# Tag201_GangProgrammerRev2.net
KiCad netlist of a schematic drawn in Altium Designer
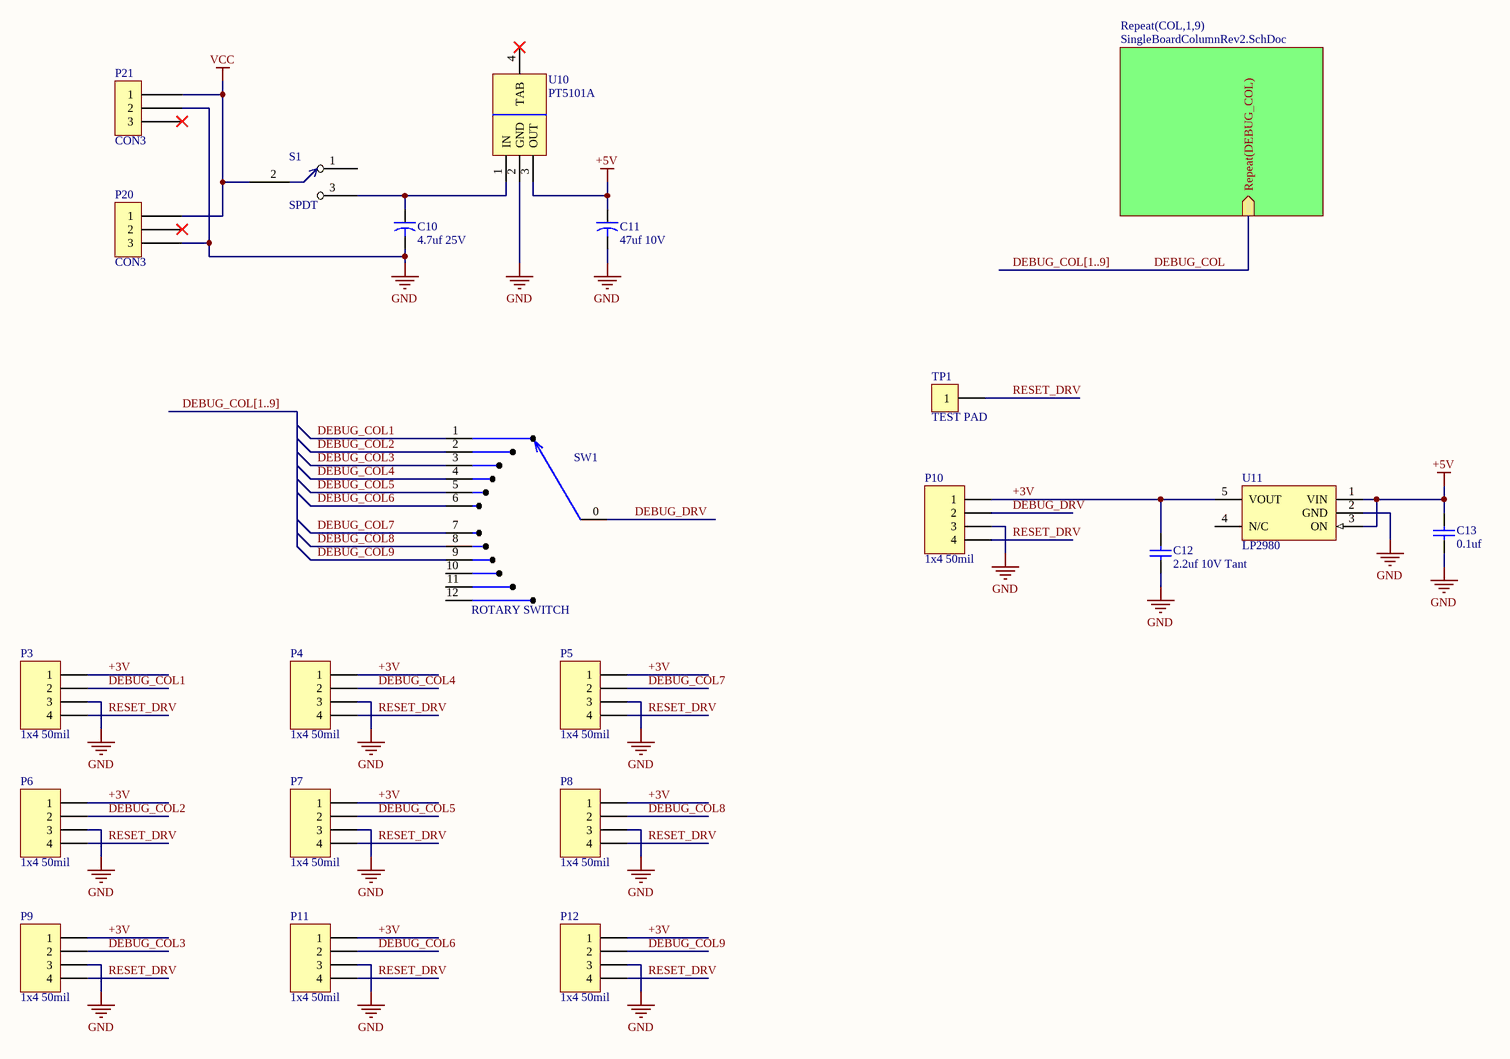
[diagram p0: Tag201_GangProgrammerRev2.SchDoc]

(export (version "E")
  (design (tool "Eeschema 10.0.6"))
  (components
    (comp (ref "C10")
      (value "4.7uf 25V")
      (footprint "CAP C CASE_041412")
      (description "Capacitor")
      (fields (field (name "PARTNO") "T491A475M025AT"))
      (libsource (lib "Miscellaneous Devices") (part "Cap2"))
    )
    (comp (ref "C11")
      (value "47uf 10V")
      (footprint "CAP D CASE_030205")
      (description "Capacitor")
      (fields (field (name "PARTNO") "TAJC476K010RNJ"))
      (libsource (lib "Miscellaneous Devices") (part "Cap2"))
    )
    (comp (ref "C12")
      (value "2.2uf 10V Tant")
      (footprint "CAP A CASE_030205")
      (description "Capacitor")
      (fields (field (name "PARTNO") "F931A225MAA"))
      (libsource (lib "Miscellaneous Devices") (part "Cap"))
    )
    (comp (ref "C13")
      (value "0.1uf")
      (footprint "0603_072205")
      (description "Capacitor")
      (fields (field (name "PARTNO") "C0603C104Z3VACTU"))
      (libsource (lib "Miscellaneous Devices") (part "Cap"))
    )
    (comp (ref "P3")
      (value "1x4 50mil")
      (footprint "1X4 HEADER_50mil_071411")
      (description "Header, 4-Pin")
      (libsource (lib "Miscellaneous Connectors") (part "Header 4"))
    )
    (comp (ref "P4")
      (value "1x4 50mil")
      (footprint "1X4 HEADER_50mil_071411")
      (description "Header, 4-Pin")
      (libsource (lib "Miscellaneous Connectors") (part "Header 4"))
    )
    (comp (ref "P5")
      (value "1x4 50mil")
      (footprint "1X4 HEADER_50mil_071411")
      (description "Header, 4-Pin")
      (libsource (lib "Miscellaneous Connectors") (part "Header 4"))
    )
    (comp (ref "P6")
      (value "1x4 50mil")
      (footprint "1X4 HEADER_50mil_071411")
      (description "Header, 4-Pin")
      (libsource (lib "Miscellaneous Connectors") (part "Header 4"))
    )
    (comp (ref "P7")
      (value "1x4 50mil")
      (footprint "1X4 HEADER_50mil_071411")
      (description "Header, 4-Pin")
      (libsource (lib "Miscellaneous Connectors") (part "Header 4"))
    )
    (comp (ref "P8")
      (value "1x4 50mil")
      (footprint "1X4 HEADER_50mil_071411")
      (description "Header, 4-Pin")
      (libsource (lib "Miscellaneous Connectors") (part "Header 4"))
    )
    (comp (ref "P9")
      (value "1x4 50mil")
      (footprint "1X4 HEADER_50mil_071411")
      (description "Header, 4-Pin")
      (libsource (lib "Miscellaneous Connectors") (part "Header 4"))
    )
    (comp (ref "P10")
      (value "1x4 50mil")
      (footprint "1X4 HEADER_50mil_071411")
      (description "Header, 4-Pin")
      (libsource (lib "Miscellaneous Connectors") (part "Header 4"))
    )
    (comp (ref "P11")
      (value "1x4 50mil")
      (footprint "1X4 HEADER_50mil_071411")
      (description "Header, 4-Pin")
      (libsource (lib "Miscellaneous Connectors") (part "Header 4"))
    )
    (comp (ref "P12")
      (value "1x4 50mil")
      (footprint "1X4 HEADER_50mil_071411")
      (description "Header, 4-Pin")
      (libsource (lib "Miscellaneous Connectors") (part "Header 4"))
    )
    (comp (ref "P20")
      (value "CON3")
      (footprint "POWER JACK_SMALLHOLE_022110")
      (fields (field (name "PARTNO") "PJ-102A"))
      (libsource (lib "Common") (part "CON3"))
    )
    (comp (ref "P21")
      (value "CON3")
      (footprint "Power Jack_SMT_071312")
      (fields (field (name "PARTNO") "PJ-002A-SMT"))
      (libsource (lib "Common") (part "CON3"))
    )
    (comp (ref "S1")
      (value "SPDT")
      (footprint "CnK_TseriesSPDT_Toggle_040512")
      (fields (field (name "PARTNO") "T102SHCQE"))
      (libsource (lib "Common") (part "SWITCH SPST"))
    )
    (comp (ref "SW1")
      (value "ROTARY SWITCH")
      (footprint "SWITCH_ROTARY_1P12T_101912")
      (fields (field (name "MFG") "Grayhill"))
      (libsource (lib "Common") (part "SwitchRotary1P12T"))
    )
    (comp (ref "TP1")
      (value "TEST PAD")
      (footprint "TestPoint52x32")
      (description "Connector")
      (libsource (lib "Common") (part "CON1"))
    )
    (comp (ref "U10")
      (value "PT5101A")
      (footprint "TI_PowerTrendsPT_061812")
      (libsource (lib "Common") (part "LM340T"))
    )
    (comp (ref "U11")
      (value "LP2980")
      (footprint "SOT25_030205")
      (fields (field (name "PARTNO") "LP2980AIM5-3.3/NOPB"))
      (libsource (lib "Common") (part "LP2985"))
    )
  )
  (nets
    (net (code "1") (name "+5V") (class "Default")
      (node (ref "C11") (pin "1") (pinfunction "1_1") (pintype "passive"))
      (node (ref "C13") (pin "1") (pinfunction "1_1") (pintype "passive"))
      (node (ref "U10") (pin "3") (pinfunction "OUT_3") (pintype "passive"))
      (node (ref "U11") (pin "1") (pinfunction "VIN_1") (pintype "power_in"))
      (node (ref "U11") (pin "3") (pinfunction "ON_3") (pintype "input"))
    )
    (net (code "2") (name "/+3V") (class "Default")
      (node (ref "C12") (pin "1") (pinfunction "1_1") (pintype "passive"))
      (node (ref "P10") (pin "1") (pinfunction "1_1") (pintype "passive"))
      (node (ref "P11") (pin "1") (pinfunction "1_1") (pintype "passive"))
      (node (ref "P12") (pin "1") (pinfunction "1_1") (pintype "passive"))
      (node (ref "P3") (pin "1") (pinfunction "1_1") (pintype "passive"))
      (node (ref "P4") (pin "1") (pinfunction "1_1") (pintype "passive"))
      (node (ref "P5") (pin "1") (pinfunction "1_1") (pintype "passive"))
      (node (ref "P6") (pin "1") (pinfunction "1_1") (pintype "passive"))
      (node (ref "P7") (pin "1") (pinfunction "1_1") (pintype "passive"))
      (node (ref "P8") (pin "1") (pinfunction "1_1") (pintype "passive"))
      (node (ref "P9") (pin "1") (pinfunction "1_1") (pintype "passive"))
      (node (ref "U11") (pin "5") (pinfunction "VOUT_5") (pintype "power_in"))
    )
    (net (code "4") (name "/DEBUG_COL1") (class "Default")
      (node (ref "P3") (pin "2") (pinfunction "2_2") (pintype "passive"))
      (node (ref "SW1") (pin "1") (pinfunction "1_1") (pintype "passive"))
    )
    (net (code "5") (name "/DEBUG_COL2") (class "Default")
      (node (ref "P6") (pin "2") (pinfunction "2_2") (pintype "passive"))
      (node (ref "SW1") (pin "2") (pinfunction "2_2") (pintype "passive"))
    )
    (net (code "6") (name "/DEBUG_COL3") (class "Default")
      (node (ref "P9") (pin "2") (pinfunction "2_2") (pintype "passive"))
      (node (ref "SW1") (pin "3") (pinfunction "3_3") (pintype "passive"))
    )
    (net (code "7") (name "/DEBUG_COL4") (class "Default")
      (node (ref "P4") (pin "2") (pinfunction "2_2") (pintype "passive"))
      (node (ref "SW1") (pin "4") (pinfunction "4_4") (pintype "passive"))
    )
    (net (code "8") (name "/DEBUG_COL5") (class "Default")
      (node (ref "P7") (pin "2") (pinfunction "2_2") (pintype "passive"))
      (node (ref "SW1") (pin "5") (pinfunction "5_5") (pintype "passive"))
    )
    (net (code "9") (name "/DEBUG_COL6") (class "Default")
      (node (ref "P11") (pin "2") (pinfunction "2_2") (pintype "passive"))
      (node (ref "SW1") (pin "6") (pinfunction "6_6") (pintype "passive"))
    )
    (net (code "10") (name "/DEBUG_COL7") (class "Default")
      (node (ref "P5") (pin "2") (pinfunction "2_2") (pintype "passive"))
      (node (ref "SW1") (pin "7") (pinfunction "7_7") (pintype "passive"))
    )
    (net (code "11") (name "/DEBUG_COL8") (class "Default")
      (node (ref "P8") (pin "2") (pinfunction "2_2") (pintype "passive"))
      (node (ref "SW1") (pin "8") (pinfunction "8_8") (pintype "passive"))
    )
    (net (code "12") (name "/DEBUG_COL9") (class "Default")
      (node (ref "P12") (pin "2") (pinfunction "2_2") (pintype "passive"))
      (node (ref "SW1") (pin "9") (pinfunction "9_9") (pintype "passive"))
    )
    (net (code "14") (name "/DEBUG_DRV") (class "Default")
      (node (ref "P10") (pin "2") (pinfunction "2_2") (pintype "passive"))
      (node (ref "SW1") (pin "0") (pinfunction "0_0") (pintype "passive"))
    )
    (net (code "15") (name "/RESET_DRV") (class "Default")
      (node (ref "P10") (pin "4") (pinfunction "4_4") (pintype "passive"))
      (node (ref "P11") (pin "4") (pinfunction "4_4") (pintype "passive"))
      (node (ref "P12") (pin "4") (pinfunction "4_4") (pintype "passive"))
      (node (ref "P3") (pin "4") (pinfunction "4_4") (pintype "passive"))
      (node (ref "P4") (pin "4") (pinfunction "4_4") (pintype "passive"))
      (node (ref "P5") (pin "4") (pinfunction "4_4") (pintype "passive"))
      (node (ref "P6") (pin "4") (pinfunction "4_4") (pintype "passive"))
      (node (ref "P7") (pin "4") (pinfunction "4_4") (pintype "passive"))
      (node (ref "P8") (pin "4") (pinfunction "4_4") (pintype "passive"))
      (node (ref "P9") (pin "4") (pinfunction "4_4") (pintype "passive"))
      (node (ref "TP1") (pin "1") (pinfunction "1_1") (pintype "passive"))
    )
    (net (code "16") (name "GND") (class "Default")
      (node (ref "C10") (pin "2") (pinfunction "2_2") (pintype "passive"))
      (node (ref "C11") (pin "2") (pinfunction "2_2") (pintype "passive"))
      (node (ref "C12") (pin "2") (pinfunction "2_2") (pintype "passive"))
      (node (ref "C13") (pin "2") (pinfunction "2_2") (pintype "passive"))
      (node (ref "P10") (pin "3") (pinfunction "3_3") (pintype "passive"))
      (node (ref "P11") (pin "3") (pinfunction "3_3") (pintype "passive"))
      (node (ref "P12") (pin "3") (pinfunction "3_3") (pintype "passive"))
      (node (ref "P20") (pin "3") (pinfunction "3_3") (pintype "passive"))
      (node (ref "P21") (pin "2") (pinfunction "2_2") (pintype "passive"))
      (node (ref "P3") (pin "3") (pinfunction "3_3") (pintype "passive"))
      (node (ref "P4") (pin "3") (pinfunction "3_3") (pintype "passive"))
      (node (ref "P5") (pin "3") (pinfunction "3_3") (pintype "passive"))
      (node (ref "P6") (pin "3") (pinfunction "3_3") (pintype "passive"))
      (node (ref "P7") (pin "3") (pinfunction "3_3") (pintype "passive"))
      (node (ref "P8") (pin "3") (pinfunction "3_3") (pintype "passive"))
      (node (ref "P9") (pin "3") (pinfunction "3_3") (pintype "passive"))
      (node (ref "U10") (pin "2") (pinfunction "GND_2") (pintype "passive"))
      (node (ref "U11") (pin "2") (pinfunction "GND_2") (pintype "power_in"))
    )
    (net (code "17") (name "Net-(U10-IN)") (class "Default")
      (node (ref "C10") (pin "1") (pinfunction "1_1") (pintype "passive"))
      (node (ref "S1") (pin "3") (pinfunction "3_3") (pintype "passive"))
      (node (ref "U10") (pin "1") (pinfunction "IN_1") (pintype "power_in"))
    )
    (net (code "18") (name "VCC") (class "Default")
      (node (ref "P20") (pin "1") (pinfunction "1_1") (pintype "passive"))
      (node (ref "P21") (pin "1") (pinfunction "1_1") (pintype "passive"))
      (node (ref "S1") (pin "2") (pinfunction "2_2") (pintype "passive"))
    )
    (net (code "19") (name "unconnected-(P20-Pad2)") (class "Default")
      (node (ref "P20") (pin "2") (pinfunction "2_2") (pintype "passive+no_connect"))
    )
    (net (code "20") (name "unconnected-(P21-Pad3)") (class "Default")
      (node (ref "P21") (pin "3") (pinfunction "3_3") (pintype "passive+no_connect"))
    )
    (net (code "21") (name "unconnected-(S1-Pad1)") (class "Default")
      (node (ref "S1") (pin "1") (pinfunction "1_1") (pintype "passive"))
    )
    (net (code "22") (name "unconnected-(SW1-Pad10)") (class "Default")
      (node (ref "SW1") (pin "10") (pinfunction "10_10") (pintype "passive"))
    )
    (net (code "23") (name "unconnected-(SW1-Pad11)") (class "Default")
      (node (ref "SW1") (pin "11") (pinfunction "11_11") (pintype "passive"))
    )
    (net (code "24") (name "unconnected-(SW1-Pad12)") (class "Default")
      (node (ref "SW1") (pin "12") (pinfunction "12_12") (pintype "passive"))
    )
    (net (code "25") (name "unconnected-(U10-TAB-Pad4)") (class "Default")
      (node (ref "U10") (pin "4") (pinfunction "TAB_4") (pintype "passive+no_connect"))
    )
    (net (code "26") (name "unconnected-(U11-N{slash}C-Pad4)") (class "Default")
      (node (ref "U11") (pin "4") (pinfunction "N/C_4") (pintype "passive"))
    )
  )
)
